# led_tester.net
KiCad netlist of a schematic drawn in EAGLE
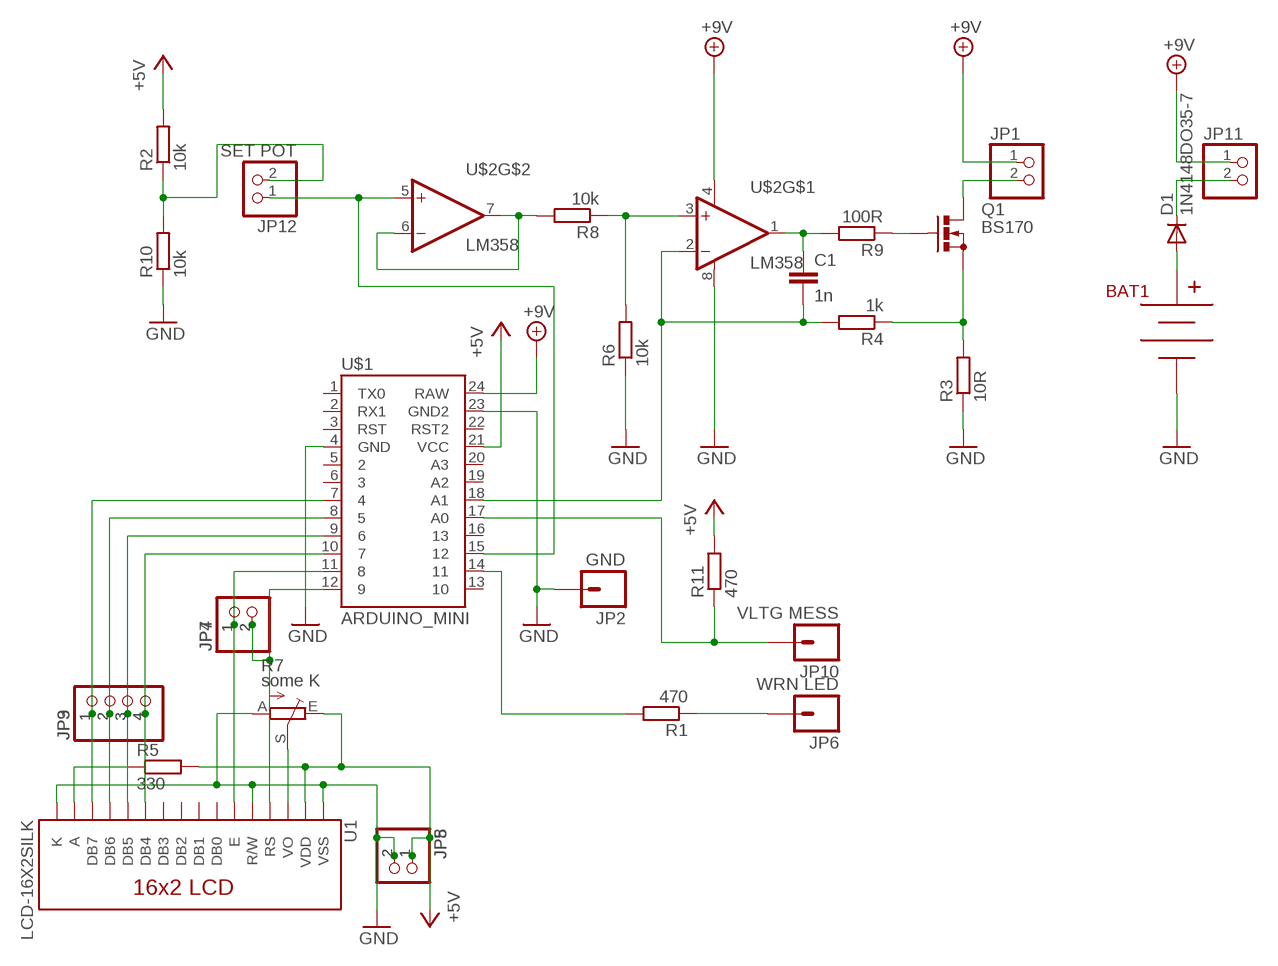
[diagram p0: schematic, sheet 1]

(export (version "E")
  (design (tool "Eeschema 10.0.6"))
  (components
    (comp (ref "BAT1")
      (value "BC9VPC")
      (footprint "eagle-import:BC9VPC")
      (libsource (lib "eagle-import") (part "BC9VPC"))
    )
    (comp (ref "C1")
      (value "1n")
      (footprint "eagle-import:C025-025X050")
      (libsource (lib "eagle-import") (part "C-EU025-025X050"))
    )
    (comp (ref "D1")
      (value "1N4148DO35-7")
      (footprint "eagle-import:DO35-7")
      (libsource (lib "eagle-import") (part "1N4148DO35-7"))
    )
    (comp (ref "JP1")
      (value "PINHD-1X2")
      (footprint "eagle-import:1X02")
      (libsource (lib "eagle-import") (part "PINHD-1X2"))
    )
    (comp (ref "JP2")
      (value "GND")
      (footprint "eagle-import:1X01_LONGPAD")
      (libsource (lib "eagle-import") (part "M01PTH_LONGPAD"))
    )
    (comp (ref "JP3")
      (value "PINHD-1X4")
      (footprint "eagle-import:1X04")
      (libsource (lib "eagle-import") (part "PINHD-1X4"))
    )
    (comp (ref "JP4")
      (value "PINHD-1X2")
      (footprint "eagle-import:1X02")
      (libsource (lib "eagle-import") (part "PINHD-1X2"))
    )
    (comp (ref "JP5")
      (value "PINHD-1X2")
      (footprint "eagle-import:1X02")
      (libsource (lib "eagle-import") (part "PINHD-1X2"))
    )
    (comp (ref "JP6")
      (value "WRN LED")
      (footprint "eagle-import:1X01_LONGPAD")
      (libsource (lib "eagle-import") (part "M01PTH_LONGPAD"))
    )
    (comp (ref "JP7")
      (value "PINHD-1X2")
      (footprint "eagle-import:1X02")
      (libsource (lib "eagle-import") (part "PINHD-1X2"))
    )
    (comp (ref "JP8")
      (value "PINHD-1X2")
      (footprint "eagle-import:1X02")
      (libsource (lib "eagle-import") (part "PINHD-1X2"))
    )
    (comp (ref "JP9")
      (value "PINHD-1X4")
      (footprint "eagle-import:1X04")
      (libsource (lib "eagle-import") (part "PINHD-1X4"))
    )
    (comp (ref "JP10")
      (value "VLTG MESS")
      (footprint "eagle-import:1X01_LONGPAD")
      (libsource (lib "eagle-import") (part "M01PTH_LONGPAD"))
    )
    (comp (ref "JP11")
      (value "PINHD-1X2")
      (footprint "eagle-import:1X02")
      (libsource (lib "eagle-import") (part "PINHD-1X2"))
    )
    (comp (ref "JP12")
      (value "SET POT")
      (footprint "eagle-import:1X02")
      (libsource (lib "eagle-import") (part "PINHD-1X2"))
    )
    (comp (ref "Q1")
      (value "BS170")
      (footprint "eagle-import:SOT54E")
      (libsource (lib "eagle-import") (part "BS170"))
    )
    (comp (ref "R1")
      (value "470")
      (footprint "eagle-import:0204_7")
      (libsource (lib "eagle-import") (part "R-EU_0204/7"))
    )
    (comp (ref "R2")
      (value "10k")
      (footprint "eagle-import:0204_7")
      (libsource (lib "eagle-import") (part "R-EU_0204/7"))
    )
    (comp (ref "R3")
      (value "10R")
      (footprint "eagle-import:0207_10")
      (libsource (lib "eagle-import") (part "R-EU_0207/10"))
    )
    (comp (ref "R4")
      (value "1k")
      (footprint "eagle-import:0204_7")
      (libsource (lib "eagle-import") (part "R-EU_0204/7"))
    )
    (comp (ref "R5")
      (value "330")
      (footprint "eagle-import:0204_7")
      (libsource (lib "eagle-import") (part "R-EU_0204/7"))
    )
    (comp (ref "R6")
      (value "10k")
      (footprint "eagle-import:0204_7")
      (libsource (lib "eagle-import") (part "R-EU_0204/7"))
    )
    (comp (ref "R7")
      (value "some K")
      (footprint "eagle-import:S63P")
      (libsource (lib "eagle-import") (part "TRIM_EU-S63P"))
    )
    (comp (ref "R8")
      (value "10k")
      (footprint "eagle-import:0204_7")
      (libsource (lib "eagle-import") (part "R-EU_0204/7"))
    )
    (comp (ref "R9")
      (value "100R")
      (footprint "eagle-import:0204_7")
      (libsource (lib "eagle-import") (part "R-EU_0204/7"))
    )
    (comp (ref "R10")
      (value "10k")
      (footprint "eagle-import:0204_7")
      (libsource (lib "eagle-import") (part "R-EU_0204/7"))
    )
    (comp (ref "R11")
      (value "470")
      (footprint "eagle-import:0204_7")
      (libsource (lib "eagle-import") (part "R-EU_0204/7"))
    )
    (comp (ref "U$1")
      (value "ARDUINO_MINI")
      (footprint "eagle-import:ARDUINO_MINI")
      (libsource (lib "eagle-import") (part "ARDUINO_MINI"))
    )
    (comp (ref "U$2")
      (value "LM358")
      (footprint "eagle-import:DIP08")
      (libsource (lib "eagle-import") (part "LM358"))
    )
    (comp (ref "U1")
      (value "LCD-16X2SILK")
      (footprint "eagle-import:LCD-16X2")
      (libsource (lib "eagle-import") (part "LCD-16X2SILK"))
    )
  )
  (nets
    (net (code "1") (name "+5V") (class "Default")
      (node (ref "JP5") (pin "1") (pinfunction "1_1") (pintype "passive"))
      (node (ref "JP8") (pin "1") (pinfunction "1_1") (pintype "passive"))
      (node (ref "R11") (pin "2") (pinfunction "2_2") (pintype "passive"))
      (node (ref "R2") (pin "2") (pinfunction "2_2") (pintype "passive"))
      (node (ref "R5") (pin "2") (pinfunction "2_2") (pintype "passive"))
      (node (ref "R7") (pin "E") (pinfunction "E_E") (pintype "passive"))
      (node (ref "U$1") (pin "21") (pinfunction "VCC_21") (pintype "bidirectional"))
      (node (ref "U1") (pin "2") (pinfunction "VDD_2") (pintype "power_in"))
    )
    (net (code "2") (name "+9V") (class "Default")
      (node (ref "JP1") (pin "1") (pinfunction "1_1") (pintype "passive"))
      (node (ref "JP11") (pin "1") (pinfunction "1_1") (pintype "passive"))
      (node (ref "U$1") (pin "24") (pinfunction "RAW_24") (pintype "bidirectional"))
      (node (ref "U$2") (pin "4") (pinfunction "V-_4") (pintype "power_in"))
    )
    (net (code "3") (name "GND") (class "Default")
      (node (ref "BAT1") (pin "V-") (pinfunction "V-_V-") (pintype "bidirectional"))
      (node (ref "JP2") (pin "1") (pinfunction "1_1") (pintype "passive"))
      (node (ref "JP5") (pin "2") (pinfunction "2_2") (pintype "passive"))
      (node (ref "JP8") (pin "2") (pinfunction "2_2") (pintype "passive"))
      (node (ref "R10") (pin "1") (pinfunction "1_1") (pintype "passive"))
      (node (ref "R3") (pin "1") (pinfunction "1_1") (pintype "passive"))
      (node (ref "R6") (pin "1") (pinfunction "1_1") (pintype "passive"))
      (node (ref "R7") (pin "A") (pinfunction "A_A") (pintype "passive"))
      (node (ref "U$1") (pin "23") (pinfunction "GND2_23") (pintype "bidirectional"))
      (node (ref "U$1") (pin "4") (pinfunction "GND_4") (pintype "bidirectional"))
      (node (ref "U$2") (pin "8") (pinfunction "V+_8") (pintype "power_in"))
      (node (ref "U1") (pin "1") (pinfunction "VSS_1") (pintype "power_in"))
      (node (ref "U1") (pin "16") (pinfunction "K_16") (pintype "power_in"))
      (node (ref "U1") (pin "5") (pinfunction "R/W_5") (pintype "input"))
    )
    (net (code "4") (name "Net-(BAT1-PadV+)") (class "Default")
      (node (ref "BAT1") (pin "V+") (pinfunction "V+_V+") (pintype "bidirectional"))
      (node (ref "D1") (pin "A") (pinfunction "A_A") (pintype "passive"))
    )
    (net (code "5") (name "Net-(D1-PadC)") (class "Default")
      (node (ref "D1") (pin "C") (pinfunction "C_C") (pintype "passive"))
      (node (ref "JP11") (pin "2") (pinfunction "2_2") (pintype "passive"))
    )
    (net (code "6") (name "Net-(JP1-Pad2)") (class "Default")
      (node (ref "JP1") (pin "2") (pinfunction "2_2") (pintype "passive"))
      (node (ref "Q1") (pin "D") (pinfunction "D_D") (pintype "passive"))
    )
    (net (code "7") (name "Net-(JP6-Pad1)") (class "Default")
      (node (ref "JP6") (pin "1") (pinfunction "1_1") (pintype "passive"))
      (node (ref "R1") (pin "1") (pinfunction "1_1") (pintype "passive"))
    )
    (net (code "8") (name "Net-(JP12-Pad2)") (class "Default")
      (node (ref "JP12") (pin "2") (pinfunction "2_2") (pintype "passive"))
      (node (ref "R10") (pin "2") (pinfunction "2_2") (pintype "passive"))
      (node (ref "R2") (pin "1") (pinfunction "1_1") (pintype "passive"))
    )
    (net (code "9") (name "Net-(Q1-PadG)") (class "Default")
      (node (ref "Q1") (pin "G") (pinfunction "G_G") (pintype "passive"))
      (node (ref "R9") (pin "1") (pinfunction "1_1") (pintype "passive"))
    )
    (net (code "10") (name "Net-(Q1-PadS)") (class "Default")
      (node (ref "Q1") (pin "S") (pinfunction "S_S") (pintype "passive"))
      (node (ref "R3") (pin "2") (pinfunction "2_2") (pintype "passive"))
      (node (ref "R4") (pin "1") (pinfunction "1_1") (pintype "passive"))
    )
    (net (code "11") (name "Net-(U$1-4)") (class "Default")
      (node (ref "JP3") (pin "1") (pinfunction "1_1") (pintype "passive"))
      (node (ref "JP9") (pin "1") (pinfunction "1_1") (pintype "passive"))
      (node (ref "U$1") (pin "7") (pinfunction "4_7") (pintype "bidirectional"))
      (node (ref "U1") (pin "14") (pinfunction "DB7_14") (pintype "bidirectional"))
    )
    (net (code "12") (name "Net-(U$1-5)") (class "Default")
      (node (ref "JP3") (pin "2") (pinfunction "2_2") (pintype "passive"))
      (node (ref "JP9") (pin "2") (pinfunction "2_2") (pintype "passive"))
      (node (ref "U$1") (pin "8") (pinfunction "5_8") (pintype "bidirectional"))
      (node (ref "U1") (pin "13") (pinfunction "DB6_13") (pintype "bidirectional"))
    )
    (net (code "13") (name "Net-(U$1-6)") (class "Default")
      (node (ref "JP3") (pin "3") (pinfunction "3_3") (pintype "passive"))
      (node (ref "JP9") (pin "3") (pinfunction "3_3") (pintype "passive"))
      (node (ref "U$1") (pin "9") (pinfunction "6_9") (pintype "bidirectional"))
      (node (ref "U1") (pin "12") (pinfunction "DB5_12") (pintype "bidirectional"))
    )
    (net (code "14") (name "Net-(U$1-7)") (class "Default")
      (node (ref "JP3") (pin "4") (pinfunction "4_4") (pintype "passive"))
      (node (ref "JP9") (pin "4") (pinfunction "4_4") (pintype "passive"))
      (node (ref "U$1") (pin "10") (pinfunction "7_10") (pintype "bidirectional"))
      (node (ref "U1") (pin "11") (pinfunction "DB4_11") (pintype "bidirectional"))
    )
    (net (code "15") (name "Net-(U$1-8)") (class "Default")
      (node (ref "JP4") (pin "1") (pinfunction "1_1") (pintype "passive"))
      (node (ref "JP7") (pin "1") (pinfunction "1_1") (pintype "passive"))
      (node (ref "U$1") (pin "11") (pinfunction "8_11") (pintype "bidirectional"))
      (node (ref "U1") (pin "6") (pinfunction "E_6") (pintype "input"))
    )
    (net (code "16") (name "Net-(U$1-9)") (class "Default")
      (node (ref "JP4") (pin "2") (pinfunction "2_2") (pintype "passive"))
      (node (ref "JP7") (pin "2") (pinfunction "2_2") (pintype "passive"))
      (node (ref "U$1") (pin "12") (pinfunction "9_12") (pintype "bidirectional"))
      (node (ref "U1") (pin "4") (pinfunction "RS_4") (pintype "input"))
    )
    (net (code "17") (name "Net-(U$1-11)") (class "Default")
      (node (ref "R1") (pin "2") (pinfunction "2_2") (pintype "passive"))
      (node (ref "U$1") (pin "14") (pinfunction "11_14") (pintype "bidirectional"))
    )
    (net (code "18") (name "Net-(U$1-12)") (class "Default")
      (node (ref "JP12") (pin "1") (pinfunction "1_1") (pintype "passive"))
      (node (ref "U$1") (pin "15") (pinfunction "12_15") (pintype "bidirectional"))
      (node (ref "U$2") (pin "5") (pinfunction "+IN_5") (pintype "input"))
    )
    (net (code "19") (name "Net-(U$1-A0)") (class "Default")
      (node (ref "JP10") (pin "1") (pinfunction "1_1") (pintype "passive"))
      (node (ref "R11") (pin "1") (pinfunction "1_1") (pintype "passive"))
      (node (ref "U$1") (pin "17") (pinfunction "A0_17") (pintype "bidirectional"))
    )
    (net (code "20") (name "Net-(U$1-A1)") (class "Default")
      (node (ref "C1") (pin "2") (pinfunction "2_2") (pintype "passive"))
      (node (ref "R4") (pin "2") (pinfunction "2_2") (pintype "passive"))
      (node (ref "U$1") (pin "18") (pinfunction "A1_18") (pintype "bidirectional"))
      (node (ref "U$2") (pin "2") (pinfunction "-IN_2") (pintype "input"))
    )
    (net (code "21") (name "Net-(U$2A-+IN)") (class "Default")
      (node (ref "R6") (pin "2") (pinfunction "2_2") (pintype "passive"))
      (node (ref "R8") (pin "1") (pinfunction "1_1") (pintype "passive"))
      (node (ref "U$2") (pin "3") (pinfunction "+IN_3") (pintype "input"))
    )
    (net (code "22") (name "Net-(U$2A-OUT)") (class "Default")
      (node (ref "C1") (pin "1") (pinfunction "1_1") (pintype "passive"))
      (node (ref "R9") (pin "2") (pinfunction "2_2") (pintype "passive"))
      (node (ref "U$2") (pin "1") (pinfunction "OUT_1") (pintype "output"))
    )
    (net (code "23") (name "Net-(U$2B--IN)") (class "Default")
      (node (ref "R8") (pin "2") (pinfunction "2_2") (pintype "passive"))
      (node (ref "U$2") (pin "6") (pinfunction "-IN_6") (pintype "input"))
      (node (ref "U$2") (pin "7") (pinfunction "OUT_7") (pintype "output"))
    )
    (net (code "24") (name "Net-(U1-A)") (class "Default")
      (node (ref "R5") (pin "1") (pinfunction "1_1") (pintype "passive"))
      (node (ref "U1") (pin "15") (pinfunction "A_15") (pintype "power_in"))
    )
    (net (code "25") (name "Net-(U1-VO)") (class "Default")
      (node (ref "R7") (pin "S") (pinfunction "S_S") (pintype "passive"))
      (node (ref "U1") (pin "3") (pinfunction "VO_3") (pintype "bidirectional"))
    )
    (net (code "26") (name "unconnected-(U$1-2-Pad5)") (class "Default")
      (node (ref "U$1") (pin "5") (pinfunction "2_5") (pintype "bidirectional"))
    )
    (net (code "27") (name "unconnected-(U$1-3-Pad6)") (class "Default")
      (node (ref "U$1") (pin "6") (pinfunction "3_6") (pintype "bidirectional"))
    )
    (net (code "28") (name "unconnected-(U$1-10-Pad13)") (class "Default")
      (node (ref "U$1") (pin "13") (pinfunction "10_13") (pintype "bidirectional"))
    )
    (net (code "29") (name "unconnected-(U$1-13-Pad16)") (class "Default")
      (node (ref "U$1") (pin "16") (pinfunction "13_16") (pintype "bidirectional"))
    )
    (net (code "30") (name "unconnected-(U$1-A2-Pad19)") (class "Default")
      (node (ref "U$1") (pin "19") (pinfunction "A2_19") (pintype "bidirectional"))
    )
    (net (code "31") (name "unconnected-(U$1-A3-Pad20)") (class "Default")
      (node (ref "U$1") (pin "20") (pinfunction "A3_20") (pintype "bidirectional"))
    )
    (net (code "32") (name "unconnected-(U$1-RST-Pad3)") (class "Default")
      (node (ref "U$1") (pin "3") (pinfunction "RST_3") (pintype "bidirectional"))
    )
    (net (code "33") (name "unconnected-(U$1-RST2-Pad22)") (class "Default")
      (node (ref "U$1") (pin "22") (pinfunction "RST2_22") (pintype "bidirectional"))
    )
    (net (code "34") (name "unconnected-(U$1-RX1-Pad2)") (class "Default")
      (node (ref "U$1") (pin "2") (pinfunction "RX1_2") (pintype "bidirectional"))
    )
    (net (code "35") (name "unconnected-(U$1-TX0-Pad1)") (class "Default")
      (node (ref "U$1") (pin "1") (pinfunction "TX0_1") (pintype "bidirectional"))
    )
    (net (code "36") (name "unconnected-(U1-DB0-Pad7)") (class "Default")
      (node (ref "U1") (pin "7") (pinfunction "DB0_7") (pintype "bidirectional"))
    )
    (net (code "37") (name "unconnected-(U1-DB1-Pad8)") (class "Default")
      (node (ref "U1") (pin "8") (pinfunction "DB1_8") (pintype "bidirectional"))
    )
    (net (code "38") (name "unconnected-(U1-DB2-Pad9)") (class "Default")
      (node (ref "U1") (pin "9") (pinfunction "DB2_9") (pintype "bidirectional"))
    )
    (net (code "39") (name "unconnected-(U1-DB3-Pad10)") (class "Default")
      (node (ref "U1") (pin "10") (pinfunction "DB3_10") (pintype "bidirectional"))
    )
  )
)
